# p2.net
KiCad netlist of a schematic drawn in EAGLE
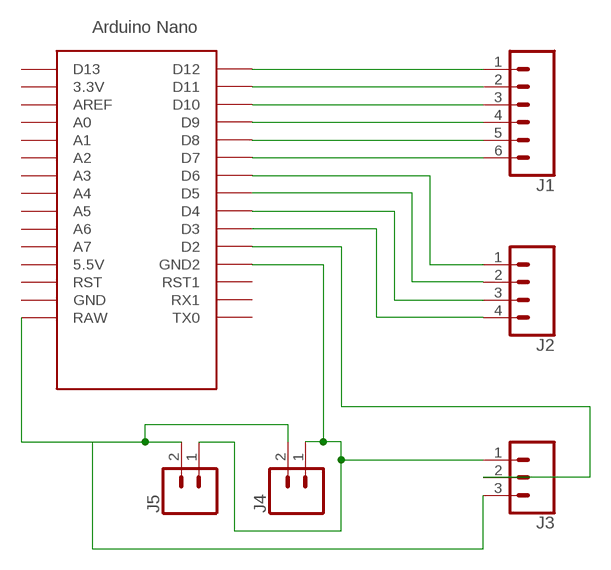
[diagram p0: schematic, sheet 1]

(export (version "E")
  (design (tool "Eeschema 10.0.6"))
  (components
    (comp (ref "J1")
      (value "CONN_06LONGPADS")
      (footprint "eagle-import:1X06_LONGPADS")
      (libsource (lib "eagle-import") (part "CONN_06LONGPADS"))
    )
    (comp (ref "J2")
      (value "CONN_04LONGPADS")
      (footprint "eagle-import:1X04_LONGPADS")
      (libsource (lib "eagle-import") (part "CONN_04LONGPADS"))
    )
    (comp (ref "J3")
      (value "CONN_03LONGPADS")
      (footprint "eagle-import:1X03_LONGPADS")
      (libsource (lib "eagle-import") (part "CONN_03LONGPADS"))
    )
    (comp (ref "J4")
      (value "CONN_02PTH3")
      (footprint "eagle-import:1X02_LONGPADS")
      (libsource (lib "eagle-import") (part "CONN_02PTH3"))
    )
    (comp (ref "J5")
      (value "CONN_02PTH3")
      (footprint "eagle-import:1X02_LONGPADS")
      (libsource (lib "eagle-import") (part "CONN_02PTH3"))
    )
    (comp (ref "U$1")
      (value "NANO")
      (footprint "eagle-import:NANO")
      (libsource (lib "eagle-import") (part "NANO"))
    )
  )
  (nets
    (net (code "1") (name "Net-(J1-Pad1)") (class "Default")
      (node (ref "J1") (pin "1") (pinfunction "1_1") (pintype "passive"))
      (node (ref "U$1") (pin "D12") (pinfunction "D12_D12") (pintype "bidirectional"))
    )
    (net (code "2") (name "Net-(J1-Pad2)") (class "Default")
      (node (ref "J1") (pin "2") (pinfunction "2_2") (pintype "passive"))
      (node (ref "U$1") (pin "D11") (pinfunction "D11_D11") (pintype "bidirectional"))
    )
    (net (code "3") (name "Net-(J1-Pad3)") (class "Default")
      (node (ref "J1") (pin "3") (pinfunction "3_3") (pintype "passive"))
      (node (ref "U$1") (pin "D10") (pinfunction "D10_D10") (pintype "bidirectional"))
    )
    (net (code "4") (name "Net-(J1-Pad4)") (class "Default")
      (node (ref "J1") (pin "4") (pinfunction "4_4") (pintype "passive"))
      (node (ref "U$1") (pin "D9") (pinfunction "D9_D9") (pintype "bidirectional"))
    )
    (net (code "5") (name "Net-(J1-Pad5)") (class "Default")
      (node (ref "J1") (pin "5") (pinfunction "5_5") (pintype "passive"))
      (node (ref "U$1") (pin "D8") (pinfunction "D8_D8") (pintype "bidirectional"))
    )
    (net (code "6") (name "Net-(J1-Pad6)") (class "Default")
      (node (ref "J1") (pin "6") (pinfunction "6_6") (pintype "passive"))
      (node (ref "U$1") (pin "D7") (pinfunction "D7_D7") (pintype "bidirectional"))
    )
    (net (code "7") (name "Net-(J2-Pad1)") (class "Default")
      (node (ref "J2") (pin "1") (pinfunction "1_1") (pintype "passive"))
      (node (ref "U$1") (pin "D6") (pinfunction "D6_D6") (pintype "bidirectional"))
    )
    (net (code "8") (name "Net-(J2-Pad2)") (class "Default")
      (node (ref "J2") (pin "2") (pinfunction "2_2") (pintype "passive"))
      (node (ref "U$1") (pin "D5") (pinfunction "D5_D5") (pintype "bidirectional"))
    )
    (net (code "9") (name "Net-(J2-Pad3)") (class "Default")
      (node (ref "J2") (pin "3") (pinfunction "3_3") (pintype "passive"))
      (node (ref "U$1") (pin "D4") (pinfunction "D4_D4") (pintype "bidirectional"))
    )
    (net (code "10") (name "Net-(J2-Pad4)") (class "Default")
      (node (ref "J2") (pin "4") (pinfunction "4_4") (pintype "passive"))
      (node (ref "U$1") (pin "D3") (pinfunction "D3_D3") (pintype "bidirectional"))
    )
    (net (code "11") (name "Net-(J3-Pad2)") (class "Default")
      (node (ref "J3") (pin "2") (pinfunction "2_2") (pintype "passive"))
      (node (ref "U$1") (pin "D2") (pinfunction "D2_D2") (pintype "bidirectional"))
    )
    (net (code "12") (name "Net-(J3-Pad3)") (class "Default")
      (node (ref "J3") (pin "3") (pinfunction "3_3") (pintype "passive"))
      (node (ref "J4") (pin "2") (pinfunction "2_2") (pintype "passive"))
      (node (ref "J5") (pin "2") (pinfunction "2_2") (pintype "passive"))
      (node (ref "U$1") (pin "RAW") (pinfunction "RAW_RAW") (pintype "bidirectional"))
    )
    (net (code "13") (name "Net-(U$1-GND2)") (class "Default")
      (node (ref "J3") (pin "1") (pinfunction "1_1") (pintype "passive"))
      (node (ref "J4") (pin "1") (pinfunction "1_1") (pintype "passive"))
      (node (ref "J5") (pin "1") (pinfunction "1_1") (pintype "passive"))
      (node (ref "U$1") (pin "GND1") (pinfunction "GND2_GND1") (pintype "bidirectional"))
    )
    (net (code "14") (name "unconnected-(U$1-5.5V-Pad5V)") (class "Default")
      (node (ref "U$1") (pin "5V") (pinfunction "5.5V_5V") (pintype "bidirectional"))
    )
    (net (code "15") (name "unconnected-(U$1-Pad3.3V)") (class "Default")
      (node (ref "U$1") (pin "3.3V") (pinfunction "3.3V_3.3V") (pintype "bidirectional"))
    )
    (net (code "16") (name "unconnected-(U$1-PadA0)") (class "Default")
      (node (ref "U$1") (pin "A0") (pinfunction "A0_A0") (pintype "bidirectional"))
    )
    (net (code "17") (name "unconnected-(U$1-PadA1)") (class "Default")
      (node (ref "U$1") (pin "A1") (pinfunction "A1_A1") (pintype "bidirectional"))
    )
    (net (code "18") (name "unconnected-(U$1-PadA2)") (class "Default")
      (node (ref "U$1") (pin "A2") (pinfunction "A2_A2") (pintype "bidirectional"))
    )
    (net (code "19") (name "unconnected-(U$1-PadA3)") (class "Default")
      (node (ref "U$1") (pin "A3") (pinfunction "A3_A3") (pintype "bidirectional"))
    )
    (net (code "20") (name "unconnected-(U$1-PadA4)") (class "Default")
      (node (ref "U$1") (pin "A4") (pinfunction "A4_A4") (pintype "bidirectional"))
    )
    (net (code "21") (name "unconnected-(U$1-PadA5)") (class "Default")
      (node (ref "U$1") (pin "A5") (pinfunction "A5_A5") (pintype "bidirectional"))
    )
    (net (code "22") (name "unconnected-(U$1-PadA6)") (class "Default")
      (node (ref "U$1") (pin "A6") (pinfunction "A6_A6") (pintype "bidirectional"))
    )
    (net (code "23") (name "unconnected-(U$1-PadA7)") (class "Default")
      (node (ref "U$1") (pin "A7") (pinfunction "A7_A7") (pintype "bidirectional"))
    )
    (net (code "24") (name "unconnected-(U$1-PadAREF)") (class "Default")
      (node (ref "U$1") (pin "AREF") (pinfunction "AREF_AREF") (pintype "bidirectional"))
    )
    (net (code "25") (name "unconnected-(U$1-PadD13)") (class "Default")
      (node (ref "U$1") (pin "D13") (pinfunction "D13_D13") (pintype "bidirectional"))
    )
    (net (code "26") (name "unconnected-(U$1-PadGND)") (class "Default")
      (node (ref "U$1") (pin "GND") (pinfunction "GND_GND") (pintype "bidirectional"))
    )
    (net (code "27") (name "unconnected-(U$1-PadICSP1)") (class "Default")
      (node (ref "U$1") (pin "ICSP1") (pinfunction "ICSP1_ICSP1") (pintype "bidirectional"))
    )
    (net (code "28") (name "unconnected-(U$1-PadICSP2)") (class "Default")
      (node (ref "U$1") (pin "ICSP2") (pinfunction "ICSP2_ICSP2") (pintype "bidirectional"))
    )
    (net (code "29") (name "unconnected-(U$1-PadICSP3)") (class "Default")
      (node (ref "U$1") (pin "ICSP3") (pinfunction "ICSP3_ICSP3") (pintype "bidirectional"))
    )
    (net (code "30") (name "unconnected-(U$1-PadICSP4)") (class "Default")
      (node (ref "U$1") (pin "ICSP4") (pinfunction "ICSP4_ICSP4") (pintype "bidirectional"))
    )
    (net (code "31") (name "unconnected-(U$1-PadICSP5)") (class "Default")
      (node (ref "U$1") (pin "ICSP5") (pinfunction "ICSP5_ICSP5") (pintype "bidirectional"))
    )
    (net (code "32") (name "unconnected-(U$1-PadICSP6)") (class "Default")
      (node (ref "U$1") (pin "ICSP6") (pinfunction "ICSP6_ICSP6") (pintype "bidirectional"))
    )
    (net (code "33") (name "unconnected-(U$1-PadRST)") (class "Default")
      (node (ref "U$1") (pin "RST") (pinfunction "RST_RST") (pintype "bidirectional"))
    )
    (net (code "34") (name "unconnected-(U$1-PadRST1)") (class "Default")
      (node (ref "U$1") (pin "RST1") (pinfunction "RST1_RST1") (pintype "bidirectional"))
    )
    (net (code "35") (name "unconnected-(U$1-PadRX1)") (class "Default")
      (node (ref "U$1") (pin "RX1") (pinfunction "RX1_RX1") (pintype "bidirectional"))
    )
    (net (code "36") (name "unconnected-(U$1-PadTX0)") (class "Default")
      (node (ref "U$1") (pin "TX0") (pinfunction "TX0_TX0") (pintype "bidirectional"))
    )
  )
)
